# Adafruit_ADS1015_ADC_STEMMA_QT.net
KiCad netlist of a schematic drawn in EAGLE
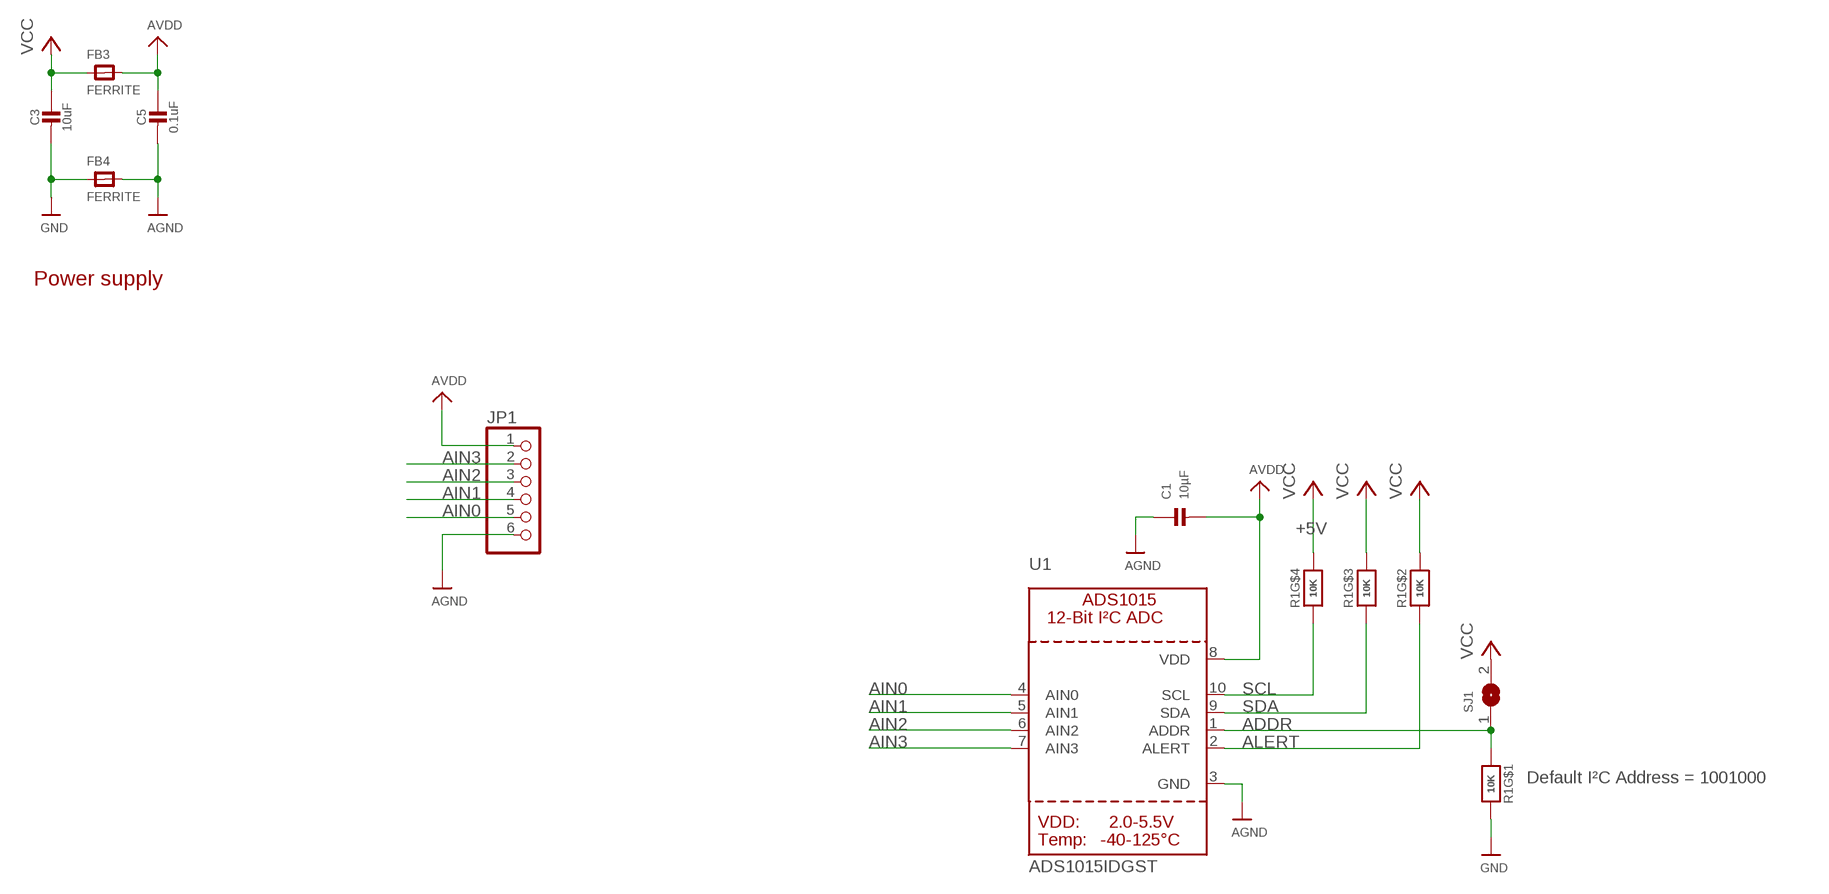
[diagram p0: schematic, sheet 1]

(export (version "E")
  (design (tool "Eeschema 10.0.6"))
  (components
    (comp (ref "C1")
      (value "10µF")
      (footprint "eagle-import:0805-NO")
      (libsource (lib "eagle-import") (part "CAP_CERAMIC0805-NOOUTLINE"))
    )
    (comp (ref "C3")
      (value "10uF")
      (footprint "eagle-import:0805-NO")
      (libsource (lib "eagle-import") (part "CAP_CERAMIC0805-NOOUTLINE"))
    )
    (comp (ref "C5")
      (value "0.1uF")
      (footprint "eagle-import:0603-NO")
      (libsource (lib "eagle-import") (part "CAP_CERAMIC0603_NO"))
    )
    (comp (ref "FB3")
      (value "FERRITE")
      (footprint "eagle-import:0603-NO")
      (libsource (lib "eagle-import") (part "FERRITE-0603NO"))
    )
    (comp (ref "FB4")
      (value "FERRITE")
      (footprint "eagle-import:0603-NO")
      (libsource (lib "eagle-import") (part "FERRITE-0603NO"))
    )
    (comp (ref "JP1")
      (value "HEADER-1X670MIL")
      (footprint "eagle-import:1X06_ROUND_70")
      (libsource (lib "eagle-import") (part "HEADER-1X670MIL"))
    )
    (comp (ref "R1")
      (value "10K")
      (footprint "eagle-import:RESPACK_4X0603")
      (libsource (lib "eagle-import") (part "RESISTOR_4PACK"))
    )
    (comp (ref "SJ1")
      (value "SOLDERJUMPER")
      (footprint "eagle-import:SOLDERJUMPER_ARROW_NOPASTE")
      (libsource (lib "eagle-import") (part "SOLDERJUMPER"))
    )
    (comp (ref "U1")
      (value "ADS1015IDGST")
      (footprint "eagle-import:MSOP10")
      (libsource (lib "eagle-import") (part "ADC_ADS1015"))
    )
  )
  (nets
    (net (code "1") (name "/ADDR") (class "Default")
      (node (ref "R1") (pin "1") (pinfunction "1_1") (pintype "passive"))
      (node (ref "SJ1") (pin "1") (pinfunction "1_1") (pintype "passive"))
      (node (ref "U1") (pin "1") (pinfunction "ADDR_1") (pintype "bidirectional"))
    )
    (net (code "2") (name "/AIN0") (class "Default")
      (node (ref "JP1") (pin "5") (pinfunction "5_5") (pintype "passive"))
      (node (ref "U1") (pin "4") (pinfunction "AIN0_4") (pintype "bidirectional"))
    )
    (net (code "3") (name "/AIN1") (class "Default")
      (node (ref "JP1") (pin "4") (pinfunction "4_4") (pintype "passive"))
      (node (ref "U1") (pin "5") (pinfunction "AIN1_5") (pintype "bidirectional"))
    )
    (net (code "4") (name "/AIN2") (class "Default")
      (node (ref "JP1") (pin "3") (pinfunction "3_3") (pintype "passive"))
      (node (ref "U1") (pin "6") (pinfunction "AIN2_6") (pintype "bidirectional"))
    )
    (net (code "5") (name "/AIN3") (class "Default")
      (node (ref "JP1") (pin "2") (pinfunction "2_2") (pintype "passive"))
      (node (ref "U1") (pin "7") (pinfunction "AIN3_7") (pintype "bidirectional"))
    )
    (net (code "6") (name "/ALERT") (class "Default")
      (node (ref "R1") (pin "2") (pinfunction "1_2") (pintype "passive"))
      (node (ref "U1") (pin "2") (pinfunction "ALERT_2") (pintype "bidirectional"))
    )
    (net (code "7") (name "/SCL") (class "Default")
      (node (ref "R1") (pin "4") (pinfunction "1_4") (pintype "passive"))
      (node (ref "U1") (pin "10") (pinfunction "SCL_10") (pintype "bidirectional"))
    )
    (net (code "8") (name "/SDA") (class "Default")
      (node (ref "R1") (pin "3") (pinfunction "1_3") (pintype "passive"))
      (node (ref "U1") (pin "9") (pinfunction "SDA_9") (pintype "bidirectional"))
    )
    (net (code "9") (name "AGND") (class "Default")
      (node (ref "C1") (pin "1") (pinfunction "1_1") (pintype "passive"))
      (node (ref "C5") (pin "2") (pinfunction "2_2") (pintype "passive"))
      (node (ref "FB4") (pin "2") (pinfunction "P$2_2") (pintype "passive"))
      (node (ref "JP1") (pin "6") (pinfunction "6_6") (pintype "passive"))
      (node (ref "U1") (pin "3") (pinfunction "GND_3") (pintype "bidirectional"))
    )
    (net (code "10") (name "AVDD") (class "Default")
      (node (ref "C1") (pin "2") (pinfunction "2_2") (pintype "passive"))
      (node (ref "C5") (pin "1") (pinfunction "1_1") (pintype "passive"))
      (node (ref "FB3") (pin "2") (pinfunction "P$2_2") (pintype "passive"))
      (node (ref "JP1") (pin "1") (pinfunction "1_1") (pintype "passive"))
      (node (ref "U1") (pin "8") (pinfunction "VDD_8") (pintype "bidirectional"))
    )
    (net (code "11") (name "GND") (class "Default")
      (node (ref "C3") (pin "2") (pinfunction "2_2") (pintype "passive"))
      (node (ref "FB4") (pin "1") (pinfunction "P$1_1") (pintype "passive"))
      (node (ref "R1") (pin "8") (pinfunction "2_8") (pintype "passive"))
    )
    (net (code "12") (name "VCC") (class "Default")
      (node (ref "C3") (pin "1") (pinfunction "1_1") (pintype "passive"))
      (node (ref "FB3") (pin "1") (pinfunction "P$1_1") (pintype "passive"))
      (node (ref "R1") (pin "5") (pinfunction "2_5") (pintype "passive"))
      (node (ref "R1") (pin "6") (pinfunction "2_6") (pintype "passive"))
      (node (ref "R1") (pin "7") (pinfunction "2_7") (pintype "passive"))
      (node (ref "SJ1") (pin "2") (pinfunction "2_2") (pintype "passive"))
    )
  )
)
